# Main-Board.net
KiCad netlist of a schematic drawn in EAGLE
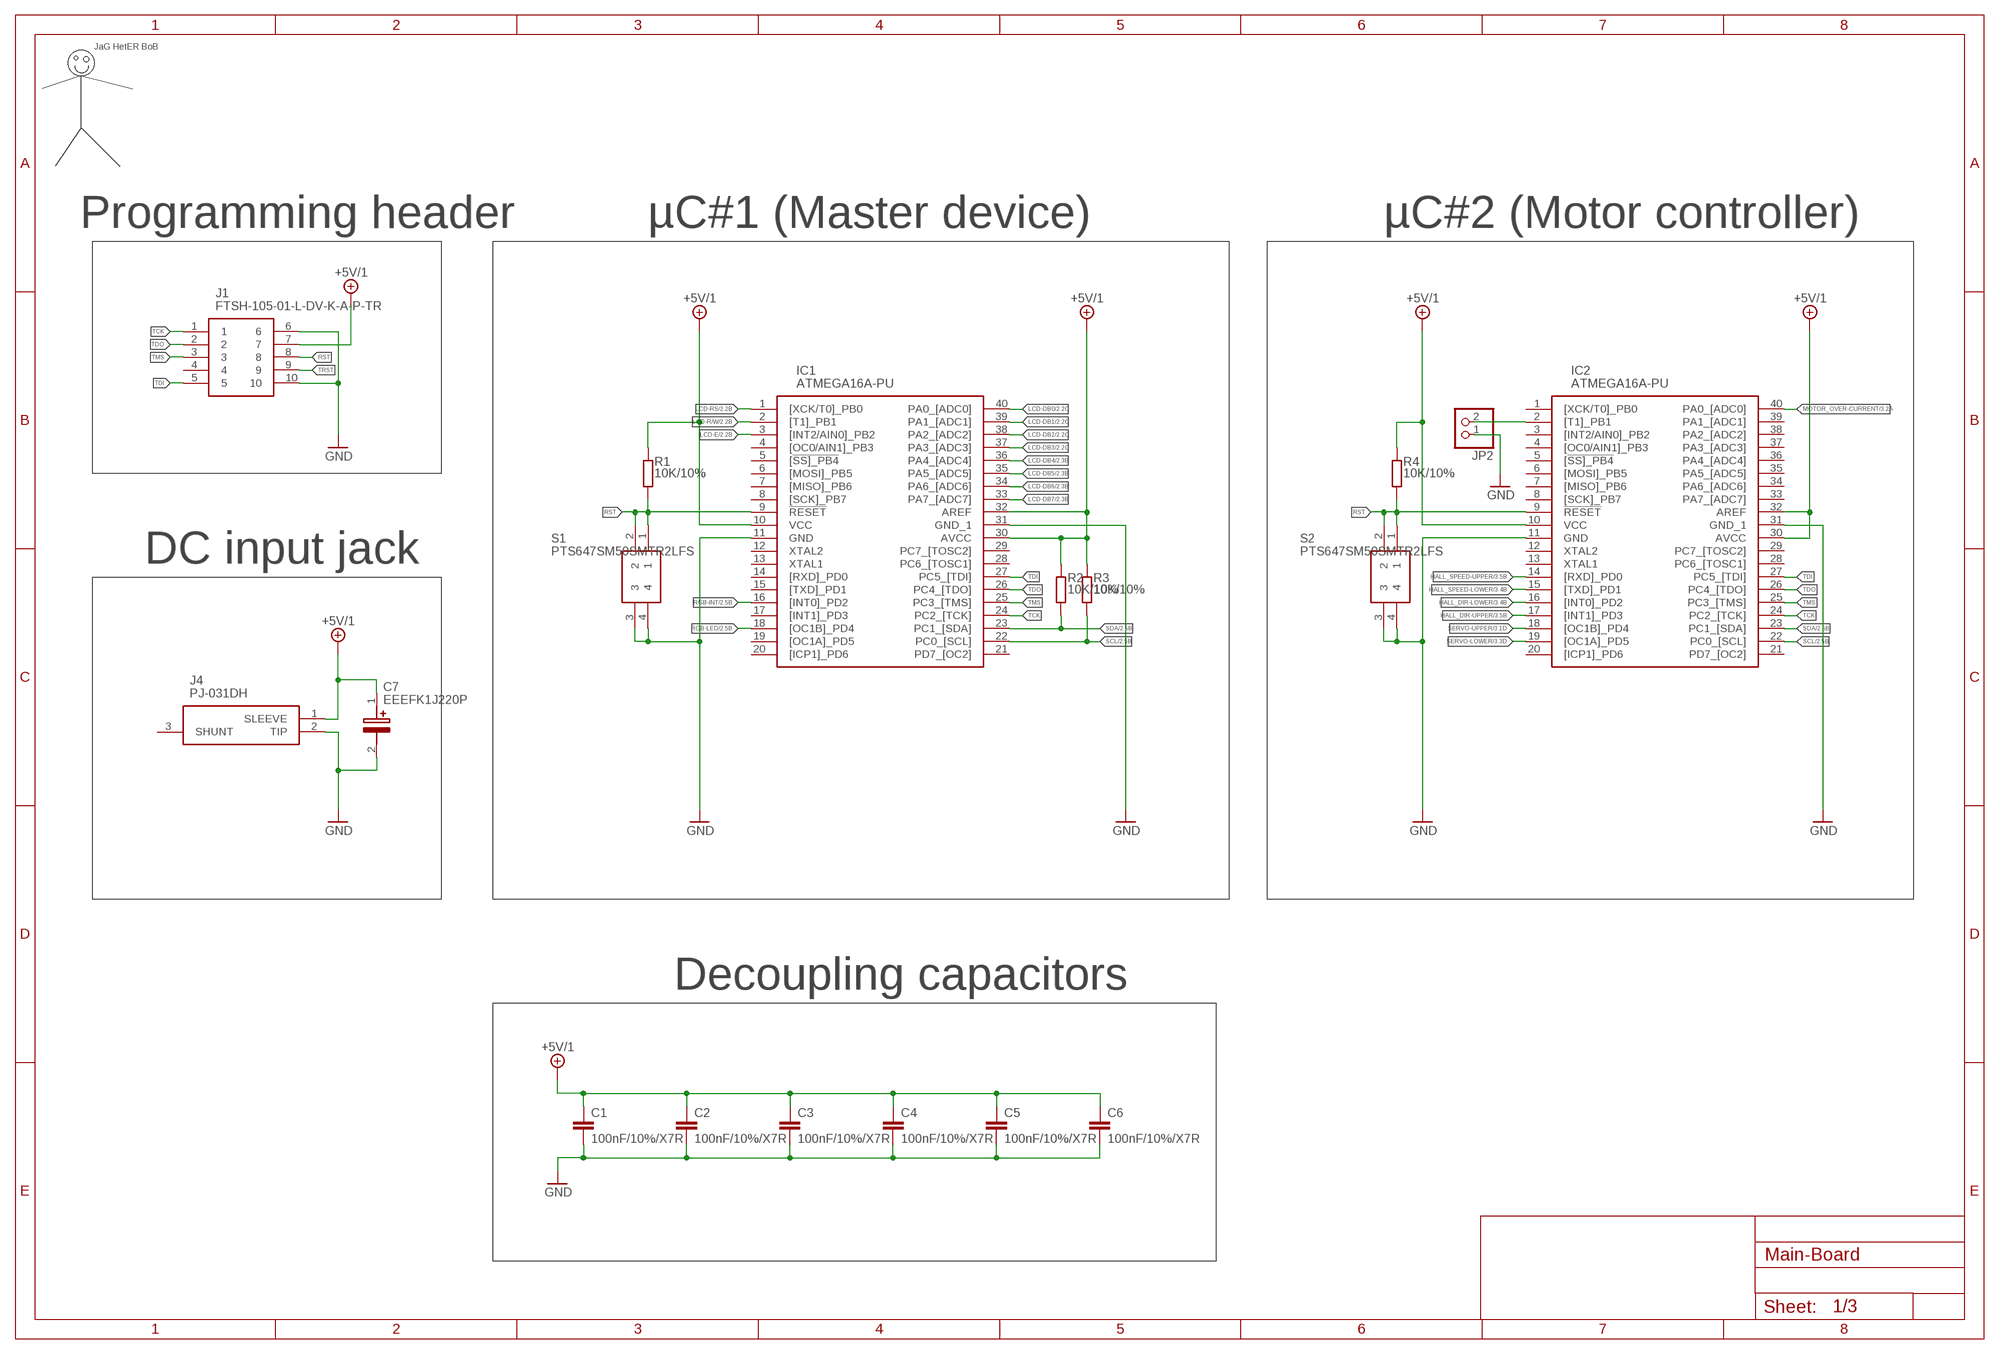
[diagram p0: schematic, sheet 1]
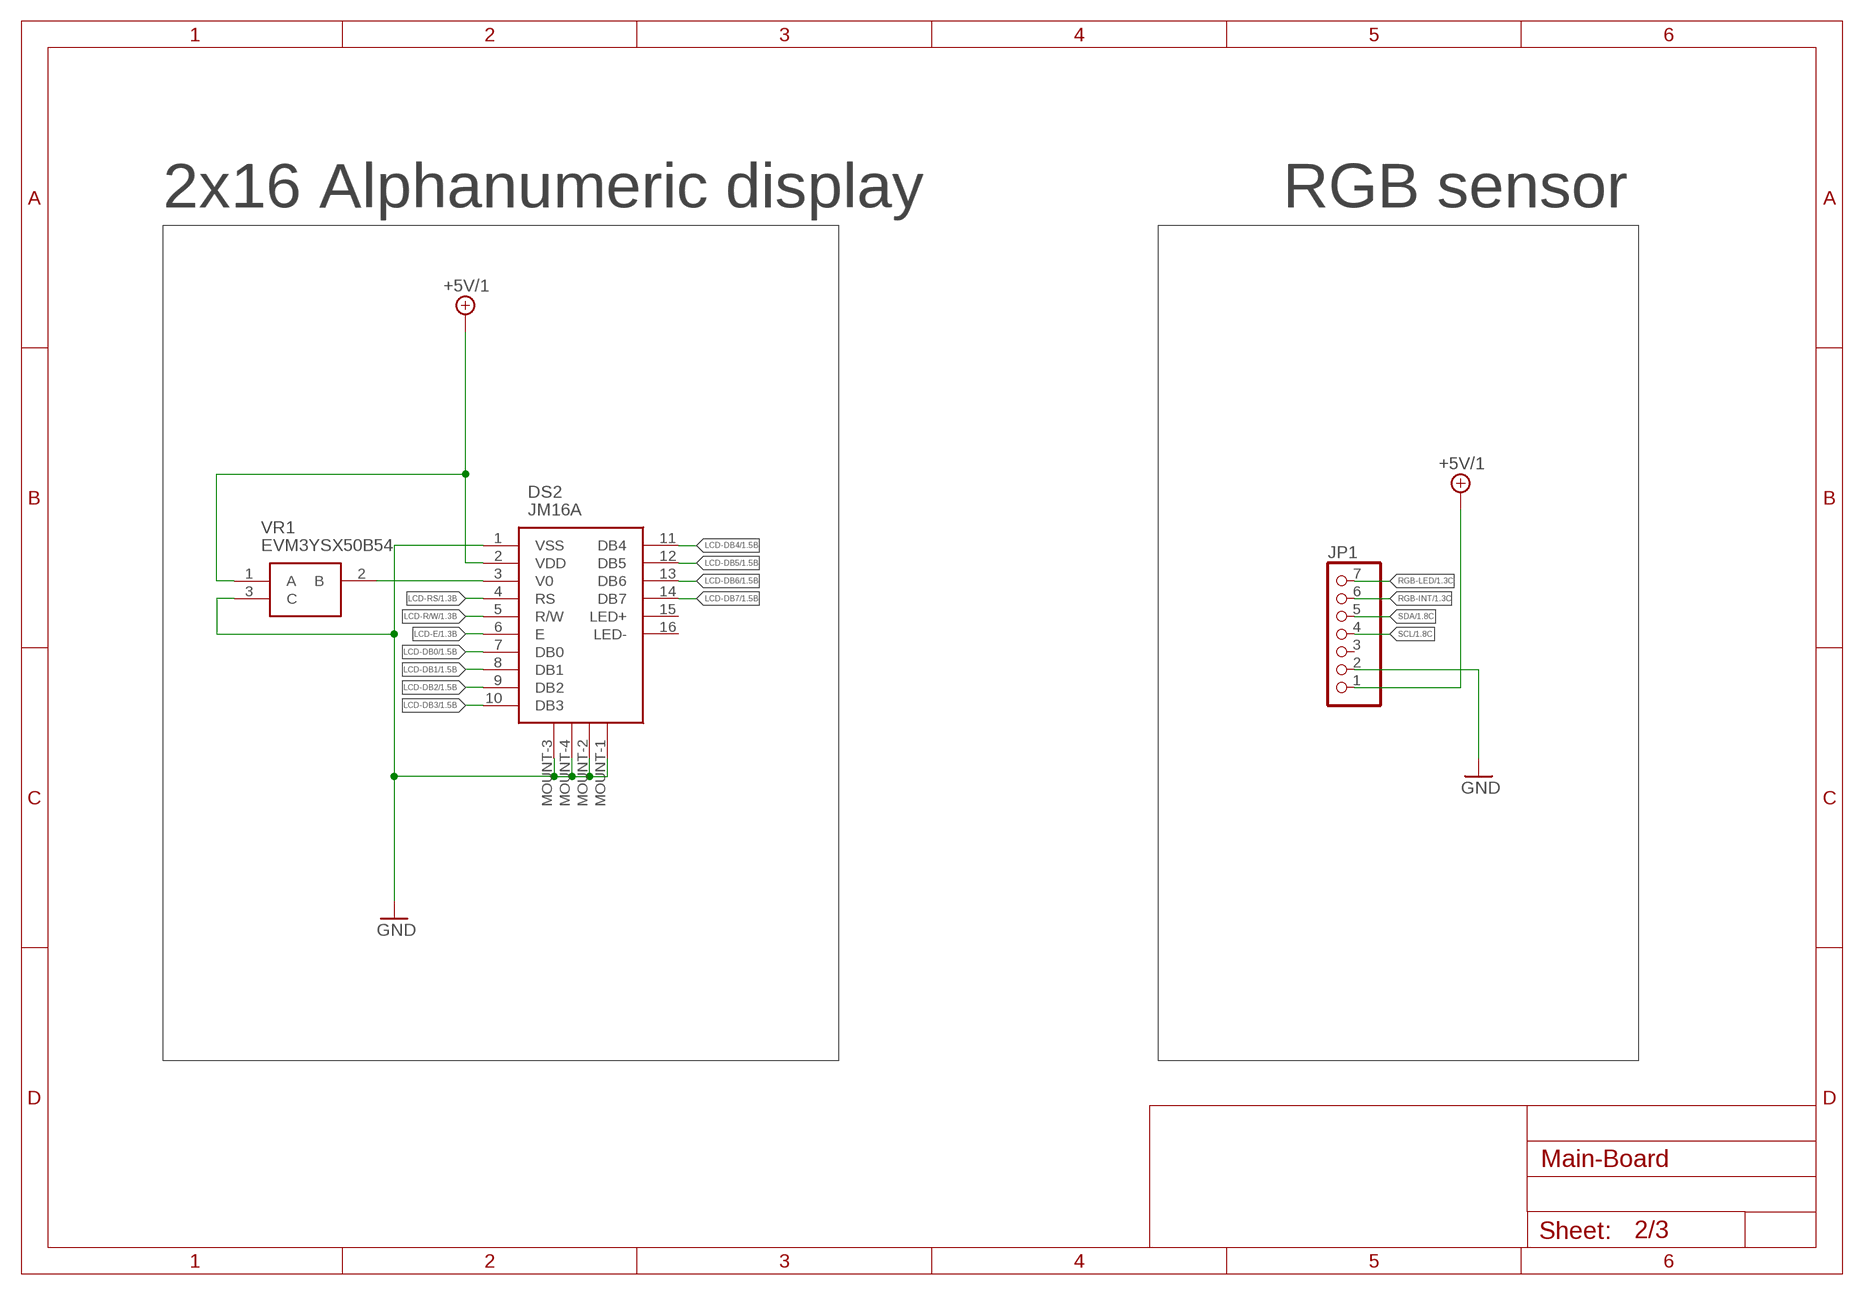
[diagram p1: schematic, sheet 2]
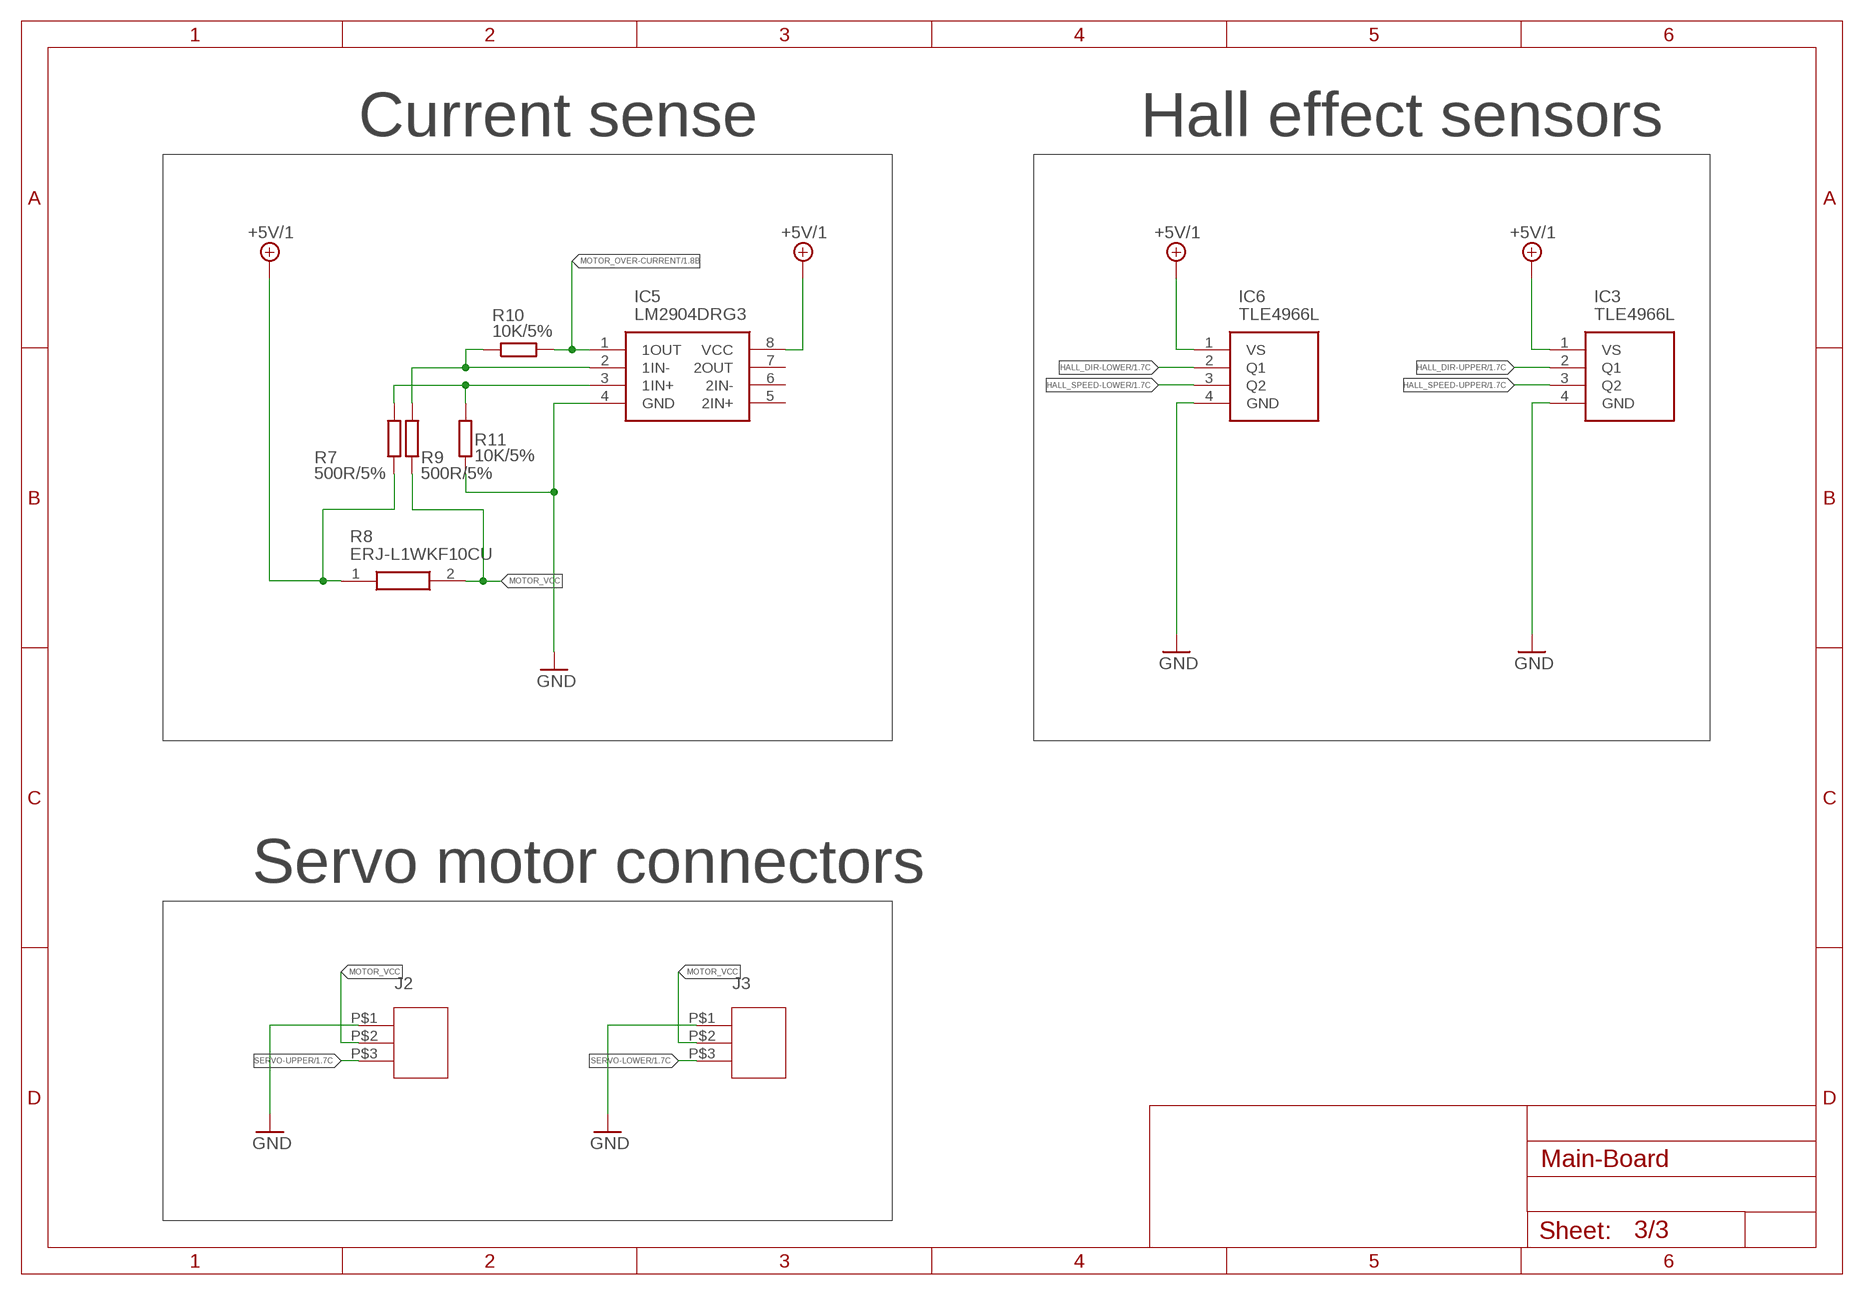
[diagram p2: schematic, sheet 3]

(export (version "E")
  (design (tool "Eeschema 10.0.6"))
  (components
    (comp (ref "C1")
      (value "100nF/10%/X7R")
      (footprint "eagle-import:C0603")
      (libsource (lib "eagle-import") (part "C-EUC0603"))
    )
    (comp (ref "C2")
      (value "100nF/10%/X7R")
      (footprint "eagle-import:C0603")
      (libsource (lib "eagle-import") (part "C-EUC0603"))
    )
    (comp (ref "C3")
      (value "100nF/10%/X7R")
      (footprint "eagle-import:C0603")
      (libsource (lib "eagle-import") (part "C-EUC0603"))
    )
    (comp (ref "C4")
      (value "100nF/10%/X7R")
      (footprint "eagle-import:C0603")
      (libsource (lib "eagle-import") (part "C-EUC0603"))
    )
    (comp (ref "C5")
      (value "100nF/10%/X7R")
      (footprint "eagle-import:C0603")
      (libsource (lib "eagle-import") (part "C-EUC0603"))
    )
    (comp (ref "C6")
      (value "100nF/10%/X7R")
      (footprint "eagle-import:C0603")
      (libsource (lib "eagle-import") (part "C-EUC0603"))
    )
    (comp (ref "C7")
      (value "EEEFK1J220P")
      (footprint "eagle-import:CAPAE800X650N")
      (fields (field (name "RS_PART_NUMBER") "7083598P"))
      (libsource (lib "eagle-import") (part "EEEFK1J220P"))
    )
    (comp (ref "IC1")
      (value "ATMEGA16A-PU")
      (footprint "eagle-import:DIP1556W56P254L5232H483Q40N")
      (fields
        (field (name "MOUSER_PART_NUMBER") "556-ATMEGA16A-PU")
        (field (name "RS_PART_NUMBER") "6962421P")
      )
      (libsource (lib "eagle-import") (part "ATMEGA16A-PU"))
    )
    (comp (ref "IC2")
      (value "ATMEGA16A-PU")
      (footprint "eagle-import:DIP1556W56P254L5232H483Q40N")
      (fields
        (field (name "MOUSER_PART_NUMBER") "556-ATMEGA16A-PU")
        (field (name "RS_PART_NUMBER") "6962421P")
      )
      (libsource (lib "eagle-import") (part "ATMEGA16A-PU"))
    )
    (comp (ref "J1")
      (value "FTSH-105-01-L-DV-K-A-P-TR")
      (footprint "eagle-import:FTSH10501LDVKAPTR")
      (fields
        (field (name "MOUSER_PART_NUMBER") "200-FTSH1051LDVKAPTR")
        (field (name "RS_PART_NUMBER") "1802978P")
      )
      (libsource (lib "eagle-import") (part "FTSH-105-01-L-DV-K-A-P-TR"))
    )
    (comp (ref "J4")
      (value "PJ-031DH")
      (footprint "eagle-import:PJ031DH")
      (fields (field (name "MOUSER_PART_NUMBER") "490-PJ-031DH"))
      (libsource (lib "eagle-import") (part "PJ-031DH"))
    )
    (comp (ref "JP2")
      (value "PINHD-1X2")
      (footprint "eagle-import:1X02")
      (libsource (lib "eagle-import") (part "PINHD-1X2"))
    )
    (comp (ref "R1")
      (value "10K/10%")
      (footprint "eagle-import:R0603")
      (libsource (lib "eagle-import") (part "R-EU_R0603"))
    )
    (comp (ref "R2")
      (value "10K/10%")
      (footprint "eagle-import:R0603")
      (libsource (lib "eagle-import") (part "R-EU_R0603"))
    )
    (comp (ref "R3")
      (value "10K/10%")
      (footprint "eagle-import:R0603")
      (libsource (lib "eagle-import") (part "R-EU_R0603"))
    )
    (comp (ref "R4")
      (value "10K/10%")
      (footprint "eagle-import:R0603")
      (libsource (lib "eagle-import") (part "R-EU_R0603"))
    )
    (comp (ref "S1")
      (value "PTS647SM50SMTR2LFS")
      (footprint "eagle-import:PTS647SM50SMTR2LFS")
      (fields (field (name "MOUSER_PART_NUMBER") "611-PTS647SM50SMTR2L"))
      (libsource (lib "eagle-import") (part "PTS647SM50SMTR2LFS"))
    )
    (comp (ref "S2")
      (value "PTS647SM50SMTR2LFS")
      (footprint "eagle-import:PTS647SM50SMTR2LFS")
      (fields (field (name "MOUSER_PART_NUMBER") "611-PTS647SM50SMTR2L"))
      (libsource (lib "eagle-import") (part "PTS647SM50SMTR2LFS"))
    )
    (comp (ref "DS2")
      (value "JM16A")
      (footprint "eagle-import:JM16A")
      (fields
        (field (name "MANUFACTURER_PART_NUMBER") "NHD-0216XZ-FSW-GBW")
        (field (name "MOUSER_PART_NUMBER") "763-0216XZ-FSW-GBW")
      )
      (libsource (lib "eagle-import") (part "JM16A"))
    )
    (comp (ref "JP1")
      (value "PINHD-1X7")
      (footprint "eagle-import:1X07")
      (libsource (lib "eagle-import") (part "PINHD-1X7"))
    )
    (comp (ref "VR1")
      (value "EVM3YSX50B54")
      (footprint "eagle-import:EVM3YSX50B54")
      (fields (field (name "RS_PART_NUMBER") "7312880"))
      (libsource (lib "eagle-import") (part "EVM3YSX50B54"))
    )
    (comp (ref "IC3")
      (value "TLE4966L")
      (footprint "eagle-import:TLE4966L")
      (fields (field (name "MOUSER_PART_NUMBER") "726-TLE4966L"))
      (libsource (lib "eagle-import") (part "TLE4966L"))
    )
    (comp (ref "IC5")
      (value "LM2904DRG3")
      (footprint "eagle-import:SOIC127P600X175-8N")
      (fields (field (name "MOUSER_PART_NUMBER") "595-LM2904DRG3"))
      (libsource (lib "eagle-import") (part "LM2904DRG3"))
    )
    (comp (ref "IC6")
      (value "TLE4966L")
      (footprint "eagle-import:TLE4966L")
      (fields (field (name "MOUSER_PART_NUMBER") "726-TLE4966L"))
      (libsource (lib "eagle-import") (part "TLE4966L"))
    )
    (comp (ref "J2")
      (value "0022288033")
      (footprint "eagle-import:0022288033")
      (libsource (lib "eagle-import") (part "0022288033"))
    )
    (comp (ref "J3")
      (value "0022288033")
      (footprint "eagle-import:0022288033")
      (libsource (lib "eagle-import") (part "0022288033"))
    )
    (comp (ref "R7")
      (value "500R/5%")
      (footprint "eagle-import:R0603")
      (libsource (lib "eagle-import") (part "R-EU_R0603"))
    )
    (comp (ref "R8")
      (value "ERJ-L1WKF10CU")
      (footprint "eagle-import:RESC6332X120N")
      (fields (field (name "MOUSER_PART_NUMBER") "667-ERJ-L1WKF10CU"))
      (libsource (lib "eagle-import") (part "ERJ-L1WKF10CU"))
    )
    (comp (ref "R9")
      (value "500R/5%")
      (footprint "eagle-import:R0603")
      (libsource (lib "eagle-import") (part "R-EU_R0603"))
    )
    (comp (ref "R10")
      (value "10K/5%")
      (footprint "eagle-import:R0603")
      (libsource (lib "eagle-import") (part "R-EU_R0603"))
    )
    (comp (ref "R11")
      (value "10K/5%")
      (footprint "eagle-import:R0603")
      (libsource (lib "eagle-import") (part "R-EU_R0603"))
    )
  )
  (nets
    (net (code "1") (name "+5V{slash}1") (class "Default")
      (node (ref "C1") (pin "1") (pinfunction "1_1") (pintype "passive"))
      (node (ref "C2") (pin "1") (pinfunction "1_1") (pintype "passive"))
      (node (ref "C3") (pin "1") (pinfunction "1_1") (pintype "passive"))
      (node (ref "C4") (pin "1") (pinfunction "1_1") (pintype "passive"))
      (node (ref "C5") (pin "1") (pinfunction "1_1") (pintype "passive"))
      (node (ref "C6") (pin "1") (pinfunction "1_1") (pintype "passive"))
      (node (ref "C7") (pin "1") (pinfunction "+_1") (pintype "bidirectional"))
      (node (ref "DS2") (pin "2") (pinfunction "VDD_2") (pintype "bidirectional"))
      (node (ref "IC1") (pin "10") (pinfunction "VCC_10") (pintype "power_in"))
      (node (ref "IC1") (pin "30") (pinfunction "AVCC_30") (pintype "power_in"))
      (node (ref "IC1") (pin "32") (pinfunction "AREF_32") (pintype "input"))
      (node (ref "IC2") (pin "10") (pinfunction "VCC_10") (pintype "power_in"))
      (node (ref "IC2") (pin "30") (pinfunction "AVCC_30") (pintype "power_in"))
      (node (ref "IC2") (pin "32") (pinfunction "AREF_32") (pintype "input"))
      (node (ref "IC3") (pin "1") (pinfunction "VS_1") (pintype "bidirectional"))
      (node (ref "IC5") (pin "8") (pinfunction "VCC_8") (pintype "bidirectional"))
      (node (ref "IC6") (pin "1") (pinfunction "VS_1") (pintype "bidirectional"))
      (node (ref "J1") (pin "7") (pinfunction "7_7") (pintype "bidirectional"))
      (node (ref "J4") (pin "1") (pinfunction "SLEEVE_1") (pintype "bidirectional"))
      (node (ref "JP1") (pin "1") (pinfunction "1_1") (pintype "passive"))
      (node (ref "R1") (pin "2") (pinfunction "2_2") (pintype "passive"))
      (node (ref "R2") (pin "2") (pinfunction "2_2") (pintype "passive"))
      (node (ref "R3") (pin "2") (pinfunction "2_2") (pintype "passive"))
      (node (ref "R4") (pin "2") (pinfunction "2_2") (pintype "passive"))
      (node (ref "R7") (pin "1") (pinfunction "1_1") (pintype "passive"))
      (node (ref "R8") (pin "1") (pinfunction "R1_1") (pintype "bidirectional"))
      (node (ref "VR1") (pin "1") (pinfunction "A_1") (pintype "bidirectional"))
    )
    (net (code "2") (name "GND") (class "Default")
      (node (ref "C1") (pin "2") (pinfunction "2_2") (pintype "passive"))
      (node (ref "C2") (pin "2") (pinfunction "2_2") (pintype "passive"))
      (node (ref "C3") (pin "2") (pinfunction "2_2") (pintype "passive"))
      (node (ref "C4") (pin "2") (pinfunction "2_2") (pintype "passive"))
      (node (ref "C5") (pin "2") (pinfunction "2_2") (pintype "passive"))
      (node (ref "C6") (pin "2") (pinfunction "2_2") (pintype "passive"))
      (node (ref "C7") (pin "2") (pinfunction "-_2") (pintype "bidirectional"))
      (node (ref "DS2") (pin "1") (pinfunction "VSS_1") (pintype "bidirectional"))
      (node (ref "DS2") (pin "MOUNT-1") (pinfunction "MOUNT-4_MOUNT-1") (pintype "bidirectional"))
      (node (ref "DS2") (pin "MOUNT-2") (pinfunction "MOUNT-3_MOUNT-2") (pintype "bidirectional"))
      (node (ref "DS2") (pin "MOUNT-3") (pinfunction "MOUNT-1_MOUNT-3") (pintype "bidirectional"))
      (node (ref "DS2") (pin "MOUNT-4") (pinfunction "MOUNT-2_MOUNT-4") (pintype "bidirectional"))
      (node (ref "IC1") (pin "11") (pinfunction "GND_11") (pintype "power_in"))
      (node (ref "IC1") (pin "31") (pinfunction "GND_1_31") (pintype "power_in"))
      (node (ref "IC2") (pin "11") (pinfunction "GND_11") (pintype "power_in"))
      (node (ref "IC2") (pin "31") (pinfunction "GND_1_31") (pintype "power_in"))
      (node (ref "IC3") (pin "4") (pinfunction "GND_4") (pintype "bidirectional"))
      (node (ref "IC5") (pin "4") (pinfunction "GND_4") (pintype "bidirectional"))
      (node (ref "IC6") (pin "4") (pinfunction "GND_4") (pintype "bidirectional"))
      (node (ref "J1") (pin "10") (pinfunction "10_10") (pintype "bidirectional"))
      (node (ref "J1") (pin "6") (pinfunction "6_6") (pintype "bidirectional"))
      (node (ref "J2") (pin "P$1") (pinfunction "1_P$1") (pintype "bidirectional"))
      (node (ref "J3") (pin "P$1") (pinfunction "1_P$1") (pintype "bidirectional"))
      (node (ref "J4") (pin "2") (pinfunction "TIP_2") (pintype "bidirectional"))
      (node (ref "JP1") (pin "2") (pinfunction "2_2") (pintype "passive"))
      (node (ref "JP2") (pin "1") (pinfunction "1_1") (pintype "passive"))
      (node (ref "R11") (pin "1") (pinfunction "1_1") (pintype "passive"))
      (node (ref "S1") (pin "3") (pinfunction "3_3") (pintype "bidirectional"))
      (node (ref "S1") (pin "4") (pinfunction "4_4") (pintype "bidirectional"))
      (node (ref "S2") (pin "3") (pinfunction "3_3") (pintype "bidirectional"))
      (node (ref "S2") (pin "4") (pinfunction "4_4") (pintype "bidirectional"))
      (node (ref "VR1") (pin "3") (pinfunction "C_3") (pintype "bidirectional"))
    )
    (net (code "3") (name "HALL_DIR-LOWER") (class "Default")
      (node (ref "IC2") (pin "16") (pinfunction "[INT0]_PD2_16") (pintype "bidirectional"))
      (node (ref "IC6") (pin "2") (pinfunction "Q1_2") (pintype "bidirectional"))
    )
    (net (code "4") (name "HALL_DIR-UPPER") (class "Default")
      (node (ref "IC2") (pin "17") (pinfunction "[INT1]_PD3_17") (pintype "bidirectional"))
      (node (ref "IC3") (pin "2") (pinfunction "Q1_2") (pintype "bidirectional"))
    )
    (net (code "5") (name "HALL_SPEED-LOWER") (class "Default")
      (node (ref "IC2") (pin "15") (pinfunction "[TXD]_PD1_15") (pintype "bidirectional"))
      (node (ref "IC6") (pin "3") (pinfunction "Q2_3") (pintype "bidirectional"))
    )
    (net (code "6") (name "HALL_SPEED-UPPER") (class "Default")
      (node (ref "IC2") (pin "14") (pinfunction "[RXD]_PD0_14") (pintype "bidirectional"))
      (node (ref "IC3") (pin "3") (pinfunction "Q2_3") (pintype "bidirectional"))
    )
    (net (code "7") (name "LCD-DB0") (class "Default")
      (node (ref "DS2") (pin "7") (pinfunction "DB0_7") (pintype "bidirectional"))
      (node (ref "IC1") (pin "40") (pinfunction "PA0_[ADC0]_40") (pintype "bidirectional"))
    )
    (net (code "8") (name "LCD-DB1") (class "Default")
      (node (ref "DS2") (pin "8") (pinfunction "DB1_8") (pintype "bidirectional"))
      (node (ref "IC1") (pin "39") (pinfunction "PA1_[ADC1]_39") (pintype "bidirectional"))
    )
    (net (code "9") (name "LCD-DB2") (class "Default")
      (node (ref "DS2") (pin "9") (pinfunction "DB2_9") (pintype "bidirectional"))
      (node (ref "IC1") (pin "38") (pinfunction "PA2_[ADC2]_38") (pintype "bidirectional"))
    )
    (net (code "10") (name "LCD-DB3") (class "Default")
      (node (ref "DS2") (pin "10") (pinfunction "DB3_10") (pintype "bidirectional"))
      (node (ref "IC1") (pin "37") (pinfunction "PA3_[ADC3]_37") (pintype "bidirectional"))
    )
    (net (code "11") (name "LCD-DB4") (class "Default")
      (node (ref "DS2") (pin "11") (pinfunction "DB4_11") (pintype "bidirectional"))
      (node (ref "IC1") (pin "36") (pinfunction "PA4_[ADC4]_36") (pintype "bidirectional"))
    )
    (net (code "12") (name "LCD-DB5") (class "Default")
      (node (ref "DS2") (pin "12") (pinfunction "DB5_12") (pintype "bidirectional"))
      (node (ref "IC1") (pin "35") (pinfunction "PA5_[ADC5]_35") (pintype "bidirectional"))
    )
    (net (code "13") (name "LCD-DB6") (class "Default")
      (node (ref "DS2") (pin "13") (pinfunction "DB6_13") (pintype "bidirectional"))
      (node (ref "IC1") (pin "34") (pinfunction "PA6_[ADC6]_34") (pintype "bidirectional"))
    )
    (net (code "14") (name "LCD-DB7") (class "Default")
      (node (ref "DS2") (pin "14") (pinfunction "DB7_14") (pintype "bidirectional"))
      (node (ref "IC1") (pin "33") (pinfunction "PA7_[ADC7]_33") (pintype "bidirectional"))
    )
    (net (code "15") (name "LCD-E") (class "Default")
      (node (ref "DS2") (pin "6") (pinfunction "E_6") (pintype "bidirectional"))
      (node (ref "IC1") (pin "3") (pinfunction "[INT2/AIN0]_PB2_3") (pintype "bidirectional"))
    )
    (net (code "16") (name "LCD-RS") (class "Default")
      (node (ref "DS2") (pin "4") (pinfunction "RS_4") (pintype "bidirectional"))
      (node (ref "IC1") (pin "1") (pinfunction "[XCK/T0]_PB0_1") (pintype "bidirectional"))
    )
    (net (code "17") (name "LCD-R{slash}W") (class "Default")
      (node (ref "DS2") (pin "5") (pinfunction "R/W_5") (pintype "bidirectional"))
      (node (ref "IC1") (pin "2") (pinfunction "[T1]_PB1_2") (pintype "bidirectional"))
    )
    (net (code "18") (name "MOTOR_OVER-CURRENT") (class "Default")
      (node (ref "IC2") (pin "40") (pinfunction "PA0_[ADC0]_40") (pintype "bidirectional"))
      (node (ref "IC5") (pin "1") (pinfunction "1OUT_1") (pintype "bidirectional"))
      (node (ref "R10") (pin "2") (pinfunction "2_2") (pintype "passive"))
    )
    (net (code "19") (name "MOTOR_VCC") (class "Default")
      (node (ref "J2") (pin "P$2") (pinfunction "2_P$2") (pintype "bidirectional"))
      (node (ref "J3") (pin "P$2") (pinfunction "2_P$2") (pintype "bidirectional"))
      (node (ref "R8") (pin "2") (pinfunction "R2_2") (pintype "bidirectional"))
      (node (ref "R9") (pin "1") (pinfunction "1_1") (pintype "passive"))
    )
    (net (code "20") (name "Net-(DS2-V0)") (class "Default")
      (node (ref "DS2") (pin "3") (pinfunction "V0_3") (pintype "bidirectional"))
      (node (ref "VR1") (pin "2") (pinfunction "B_2") (pintype "bidirectional"))
    )
    (net (code "21") (name "Net-(IC2-[T1]_PB1)") (class "Default")
      (node (ref "IC2") (pin "2") (pinfunction "[T1]_PB1_2") (pintype "bidirectional"))
      (node (ref "JP2") (pin "2") (pinfunction "2_2") (pintype "passive"))
    )
    (net (code "22") (name "Net-(IC5-1IN+)") (class "Default")
      (node (ref "IC5") (pin "3") (pinfunction "1IN+_3") (pintype "bidirectional"))
      (node (ref "R11") (pin "2") (pinfunction "2_2") (pintype "passive"))
      (node (ref "R7") (pin "2") (pinfunction "2_2") (pintype "passive"))
    )
    (net (code "23") (name "Net-(IC5-1IN-)") (class "Default")
      (node (ref "IC5") (pin "2") (pinfunction "1IN-_2") (pintype "bidirectional"))
      (node (ref "R10") (pin "1") (pinfunction "1_1") (pintype "passive"))
      (node (ref "R9") (pin "2") (pinfunction "2_2") (pintype "passive"))
    )
    (net (code "24") (name "RGB-INT") (class "Default")
      (node (ref "IC1") (pin "16") (pinfunction "[INT0]_PD2_16") (pintype "bidirectional"))
      (node (ref "JP1") (pin "6") (pinfunction "6_6") (pintype "passive"))
    )
    (net (code "25") (name "RGB-LED") (class "Default")
      (node (ref "IC1") (pin "18") (pinfunction "[OC1B]_PD4_18") (pintype "bidirectional"))
      (node (ref "JP1") (pin "7") (pinfunction "7_7") (pintype "passive"))
    )
    (net (code "26") (name "RST") (class "Default")
      (node (ref "IC1") (pin "9") (pinfunction "~{RESET}_9") (pintype "input"))
      (node (ref "IC2") (pin "9") (pinfunction "~{RESET}_9") (pintype "input"))
      (node (ref "J1") (pin "8") (pinfunction "8_8") (pintype "bidirectional"))
      (node (ref "R1") (pin "1") (pinfunction "1_1") (pintype "passive"))
      (node (ref "R4") (pin "1") (pinfunction "1_1") (pintype "passive"))
      (node (ref "S1") (pin "1") (pinfunction "1_1") (pintype "bidirectional"))
      (node (ref "S1") (pin "2") (pinfunction "2_2") (pintype "bidirectional"))
      (node (ref "S2") (pin "1") (pinfunction "1_1") (pintype "bidirectional"))
      (node (ref "S2") (pin "2") (pinfunction "2_2") (pintype "bidirectional"))
    )
    (net (code "27") (name "SCL") (class "Default")
      (node (ref "IC1") (pin "22") (pinfunction "PC0_[SCL]_22") (pintype "bidirectional"))
      (node (ref "IC2") (pin "22") (pinfunction "PC0_[SCL]_22") (pintype "bidirectional"))
      (node (ref "JP1") (pin "4") (pinfunction "4_4") (pintype "passive"))
      (node (ref "R3") (pin "1") (pinfunction "1_1") (pintype "passive"))
    )
    (net (code "28") (name "SDA") (class "Default")
      (node (ref "IC1") (pin "23") (pinfunction "PC1_[SDA]_23") (pintype "bidirectional"))
      (node (ref "IC2") (pin "23") (pinfunction "PC1_[SDA]_23") (pintype "bidirectional"))
      (node (ref "JP1") (pin "5") (pinfunction "5_5") (pintype "passive"))
      (node (ref "R2") (pin "1") (pinfunction "1_1") (pintype "passive"))
    )
    (net (code "29") (name "SERVO-LOWER") (class "Default")
      (node (ref "IC2") (pin "19") (pinfunction "[OC1A]_PD5_19") (pintype "bidirectional"))
      (node (ref "J3") (pin "P$3") (pinfunction "3_P$3") (pintype "bidirectional"))
    )
    (net (code "30") (name "SERVO-UPPER") (class "Default")
      (node (ref "IC2") (pin "18") (pinfunction "[OC1B]_PD4_18") (pintype "bidirectional"))
      (node (ref "J2") (pin "P$3") (pinfunction "3_P$3") (pintype "bidirectional"))
    )
    (net (code "31") (name "TCK") (class "Default")
      (node (ref "IC1") (pin "24") (pinfunction "PC2_[TCK]_24") (pintype "bidirectional"))
      (node (ref "IC2") (pin "24") (pinfunction "PC2_[TCK]_24") (pintype "bidirectional"))
      (node (ref "J1") (pin "1") (pinfunction "1_1") (pintype "bidirectional"))
    )
    (net (code "32") (name "TDI") (class "Default")
      (node (ref "IC1") (pin "27") (pinfunction "PC5_[TDI]_27") (pintype "bidirectional"))
      (node (ref "IC2") (pin "27") (pinfunction "PC5_[TDI]_27") (pintype "bidirectional"))
      (node (ref "J1") (pin "5") (pinfunction "5_5") (pintype "bidirectional"))
    )
    (net (code "33") (name "TDO") (class "Default")
      (node (ref "IC1") (pin "26") (pinfunction "PC4_[TDO]_26") (pintype "bidirectional"))
      (node (ref "IC2") (pin "26") (pinfunction "PC4_[TDO]_26") (pintype "bidirectional"))
      (node (ref "J1") (pin "2") (pinfunction "2_2") (pintype "bidirectional"))
    )
    (net (code "34") (name "TMS") (class "Default")
      (node (ref "IC1") (pin "25") (pinfunction "PC3_[TMS]_25") (pintype "bidirectional"))
      (node (ref "IC2") (pin "25") (pinfunction "PC3_[TMS]_25") (pintype "bidirectional"))
      (node (ref "J1") (pin "3") (pinfunction "3_3") (pintype "bidirectional"))
    )
    (net (code "35") (name "TRST") (class "Default")
      (node (ref "J1") (pin "9") (pinfunction "9_9") (pintype "bidirectional"))
    )
    (net (code "36") (name "unconnected-(DS2-LED+-Pad15)") (class "Default")
      (node (ref "DS2") (pin "15") (pinfunction "LED+_15") (pintype "bidirectional"))
    )
    (net (code "37") (name "unconnected-(DS2-LED--Pad16)") (class "Default")
      (node (ref "DS2") (pin "16") (pinfunction "LED-_16") (pintype "bidirectional"))
    )
    (net (code "38") (name "unconnected-(IC1-PC6_[TOSC1]-Pad28)") (class "Default")
      (node (ref "IC1") (pin "28") (pinfunction "PC6_[TOSC1]_28") (pintype "bidirectional"))
    )
    (net (code "39") (name "unconnected-(IC1-PC7_[TOSC2]-Pad29)") (class "Default")
      (node (ref "IC1") (pin "29") (pinfunction "PC7_[TOSC2]_29") (pintype "bidirectional"))
    )
    (net (code "40") (name "unconnected-(IC1-PD7_[OC2]-Pad21)") (class "Default")
      (node (ref "IC1") (pin "21") (pinfunction "PD7_[OC2]_21") (pintype "bidirectional"))
    )
    (net (code "41") (name "unconnected-(IC1-XTAL1-Pad13)") (class "Default")
      (node (ref "IC1") (pin "13") (pinfunction "XTAL1_13") (pintype "input"))
    )
    (net (code "42") (name "unconnected-(IC1-XTAL2-Pad12)") (class "Default")
      (node (ref "IC1") (pin "12") (pinfunction "XTAL2_12") (pintype "output"))
    )
    (net (code "43") (name "unconnected-(IC1-[ICP1]_PD6-Pad20)") (class "Default")
      (node (ref "IC1") (pin "20") (pinfunction "[ICP1]_PD6_20") (pintype "bidirectional"))
    )
    (net (code "44") (name "unconnected-(IC1-[INT1]_PD3-Pad17)") (class "Default")
      (node (ref "IC1") (pin "17") (pinfunction "[INT1]_PD3_17") (pintype "bidirectional"))
    )
    (net (code "45") (name "unconnected-(IC1-[MISO]_PB6-Pad7)") (class "Default")
      (node (ref "IC1") (pin "7") (pinfunction "[MISO]_PB6_7") (pintype "bidirectional"))
    )
    (net (code "46") (name "unconnected-(IC1-[MOSI]_PB5-Pad6)") (class "Default")
      (node (ref "IC1") (pin "6") (pinfunction "[MOSI]_PB5_6") (pintype "bidirectional"))
    )
    (net (code "47") (name "unconnected-(IC1-[OC0{slash}AIN1]_PB3-Pad4)") (class "Default")
      (node (ref "IC1") (pin "4") (pinfunction "[OC0/AIN1]_PB3_4") (pintype "bidirectional"))
    )
    (net (code "48") (name "unconnected-(IC1-[OC1A]_PD5-Pad19)") (class "Default")
      (node (ref "IC1") (pin "19") (pinfunction "[OC1A]_PD5_19") (pintype "bidirectional"))
    )
    (net (code "49") (name "unconnected-(IC1-[RXD]_PD0-Pad14)") (class "Default")
      (node (ref "IC1") (pin "14") (pinfunction "[RXD]_PD0_14") (pintype "bidirectional"))
    )
    (net (code "50") (name "unconnected-(IC1-[SCK]_PB7-Pad8)") (class "Default")
      (node (ref "IC1") (pin "8") (pinfunction "[SCK]_PB7_8") (pintype "bidirectional"))
    )
    (net (code "51") (name "unconnected-(IC1-[TXD]_PD1-Pad15)") (class "Default")
      (node (ref "IC1") (pin "15") (pinfunction "[TXD]_PD1_15") (pintype "bidirectional"))
    )
    (net (code "52") (name "unconnected-(IC1-[~{SS]_PB4}-Pad5)") (class "Default")
      (node (ref "IC1") (pin "5") (pinfunction "[~{SS]_PB4}_5") (pintype "bidirectional"))
    )
    (net (code "53") (name "unconnected-(IC2-PA1_[ADC1]-Pad39)") (class "Default")
      (node (ref "IC2") (pin "39") (pinfunction "PA1_[ADC1]_39") (pintype "bidirectional"))
    )
    (net (code "54") (name "unconnected-(IC2-PA2_[ADC2]-Pad38)") (class "Default")
      (node (ref "IC2") (pin "38") (pinfunction "PA2_[ADC2]_38") (pintype "bidirectional"))
    )
    (net (code "55") (name "unconnected-(IC2-PA3_[ADC3]-Pad37)") (class "Default")
      (node (ref "IC2") (pin "37") (pinfunction "PA3_[ADC3]_37") (pintype "bidirectional"))
    )
    (net (code "56") (name "unconnected-(IC2-PA4_[ADC4]-Pad36)") (class "Default")
      (node (ref "IC2") (pin "36") (pinfunction "PA4_[ADC4]_36") (pintype "bidirectional"))
    )
    (net (code "57") (name "unconnected-(IC2-PA5_[ADC5]-Pad35)") (class "Default")
      (node (ref "IC2") (pin "35") (pinfunction "PA5_[ADC5]_35") (pintype "bidirectional"))
    )
    (net (code "58") (name "unconnected-(IC2-PA6_[ADC6]-Pad34)") (class "Default")
      (node (ref "IC2") (pin "34") (pinfunction "PA6_[ADC6]_34") (pintype "bidirectional"))
    )
    (net (code "59") (name "unconnected-(IC2-PA7_[ADC7]-Pad33)") (class "Default")
      (node (ref "IC2") (pin "33") (pinfunction "PA7_[ADC7]_33") (pintype "bidirectional"))
    )
    (net (code "60") (name "unconnected-(IC2-PC6_[TOSC1]-Pad28)") (class "Default")
      (node (ref "IC2") (pin "28") (pinfunction "PC6_[TOSC1]_28") (pintype "bidirectional"))
    )
    (net (code "61") (name "unconnected-(IC2-PC7_[TOSC2]-Pad29)") (class "Default")
      (node (ref "IC2") (pin "29") (pinfunction "PC7_[TOSC2]_29") (pintype "bidirectional"))
    )
    (net (code "62") (name "unconnected-(IC2-PD7_[OC2]-Pad21)") (class "Default")
      (node (ref "IC2") (pin "21") (pinfunction "PD7_[OC2]_21") (pintype "bidirectional"))
    )
    (net (code "63") (name "unconnected-(IC2-XTAL1-Pad13)") (class "Default")
      (node (ref "IC2") (pin "13") (pinfunction "XTAL1_13") (pintype "input"))
    )
    (net (code "64") (name "unconnected-(IC2-XTAL2-Pad12)") (class "Default")
      (node (ref "IC2") (pin "12") (pinfunction "XTAL2_12") (pintype "output"))
    )
    (net (code "65") (name "unconnected-(IC2-[ICP1]_PD6-Pad20)") (class "Default")
      (node (ref "IC2") (pin "20") (pinfunction "[ICP1]_PD6_20") (pintype "bidirectional"))
    )
    (net (code "66") (name "unconnected-(IC2-[INT2{slash}AIN0]_PB2-Pad3)") (class "Default")
      (node (ref "IC2") (pin "3") (pinfunction "[INT2/AIN0]_PB2_3") (pintype "bidirectional"))
    )
    (net (code "67") (name "unconnected-(IC2-[MISO]_PB6-Pad7)") (class "Default")
      (node (ref "IC2") (pin "7") (pinfunction "[MISO]_PB6_7") (pintype "bidirectional"))
    )
    (net (code "68") (name "unconnected-(IC2-[MOSI]_PB5-Pad6)") (class "Default")
      (node (ref "IC2") (pin "6") (pinfunction "[MOSI]_PB5_6") (pintype "bidirectional"))
    )
    (net (code "69") (name "unconnected-(IC2-[OC0{slash}AIN1]_PB3-Pad4)") (class "Default")
      (node (ref "IC2") (pin "4") (pinfunction "[OC0/AIN1]_PB3_4") (pintype "bidirectional"))
    )
    (net (code "70") (name "unconnected-(IC2-[SCK]_PB7-Pad8)") (class "Default")
      (node (ref "IC2") (pin "8") (pinfunction "[SCK]_PB7_8") (pintype "bidirectional"))
    )
    (net (code "71") (name "unconnected-(IC2-[XCK{slash}T0]_PB0-Pad1)") (class "Default")
      (node (ref "IC2") (pin "1") (pinfunction "[XCK/T0]_PB0_1") (pintype "bidirectional"))
    )
    (net (code "72") (name "unconnected-(IC2-[~{SS]_PB4}-Pad5)") (class "Default")
      (node (ref "IC2") (pin "5") (pinfunction "[~{SS]_PB4}_5") (pintype "bidirectional"))
    )
    (net (code "73") (name "unconnected-(IC5-2IN+-Pad5)") (class "Default")
      (node (ref "IC5") (pin "5") (pinfunction "2IN+_5") (pintype "bidirectional"))
    )
    (net (code "74") (name "unconnected-(IC5-2IN--Pad6)") (class "Default")
      (node (ref "IC5") (pin "6") (pinfunction "2IN-_6") (pintype "bidirectional"))
    )
    (net (code "75") (name "unconnected-(IC5-2OUT-Pad7)") (class "Default")
      (node (ref "IC5") (pin "7") (pinfunction "2OUT_7") (pintype "bidirectional"))
    )
    (net (code "76") (name "unconnected-(J1-Pad4)") (class "Default")
      (node (ref "J1") (pin "4") (pinfunction "4_4") (pintype "bidirectional"))
    )
    (net (code "77") (name "unconnected-(J4-SHUNT-Pad3)") (class "Default")
      (node (ref "J4") (pin "3") (pinfunction "SHUNT_3") (pintype "bidirectional"))
    )
    (net (code "78") (name "unconnected-(JP1-Pad3)") (class "Default")
      (node (ref "JP1") (pin "3") (pinfunction "3_3") (pintype "passive"))
    )
  )
)
